# power_unit.net
KiCad netlist of a schematic drawn in Altium Designer
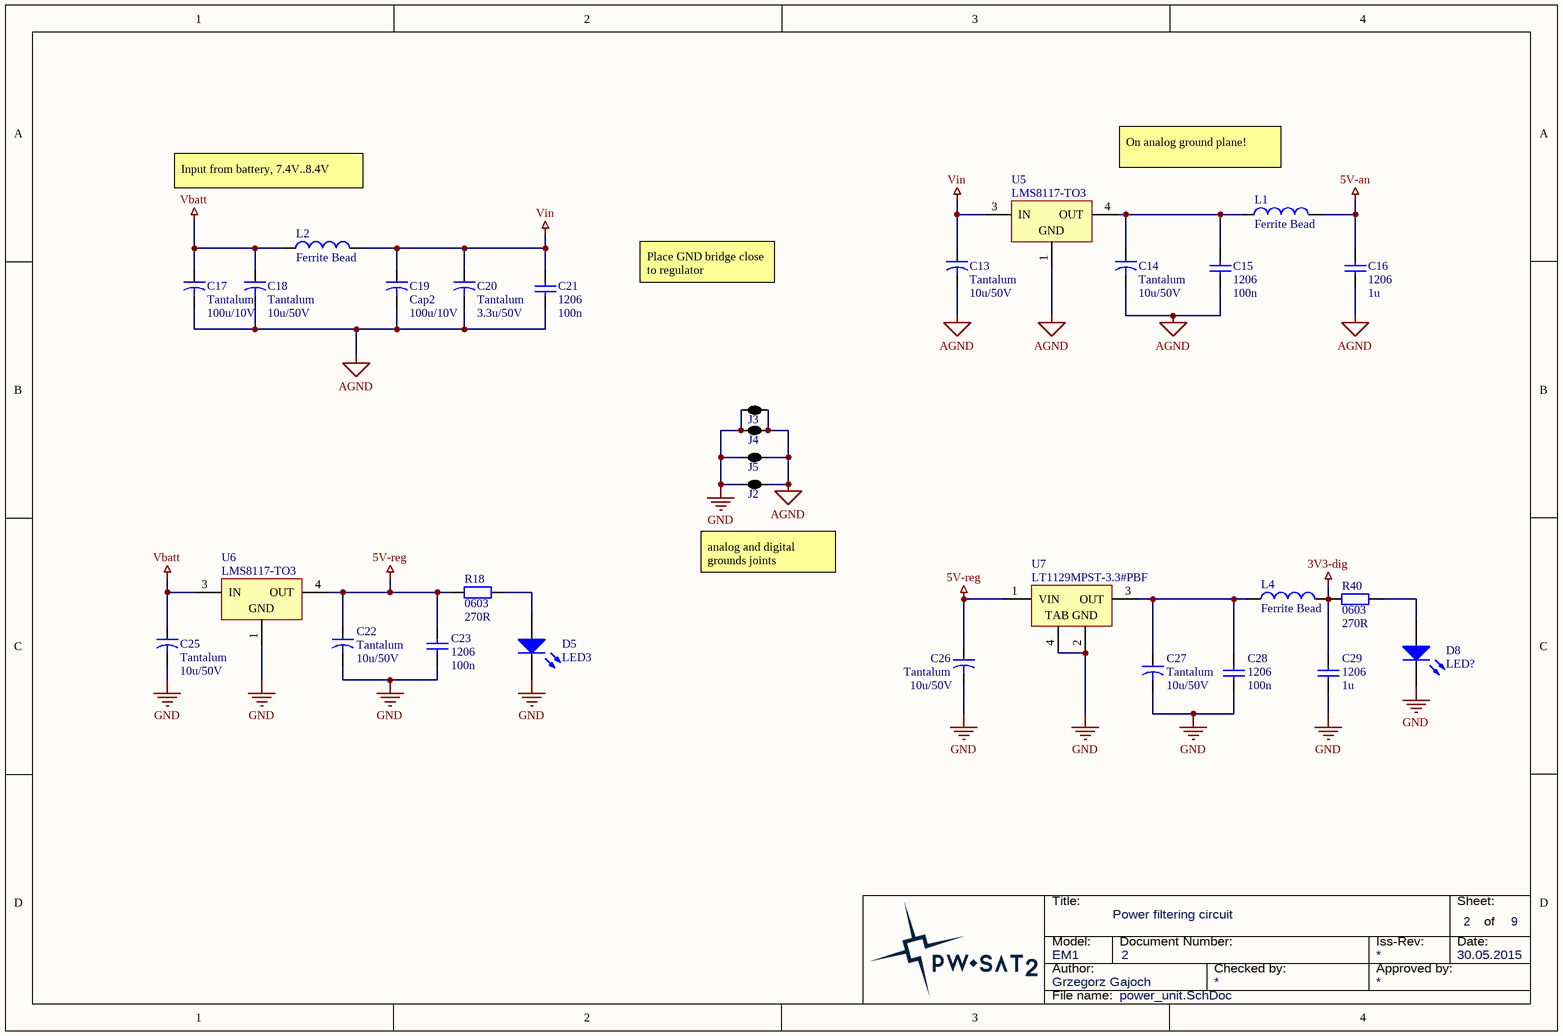
[diagram p0: power_unit.SchDoc]

(export (version "E")
  (design (tool "Eeschema 10.0.6"))
  (components
    (comp (ref "C13")
      (value "Tantalum")
      (footprint "Tantalum_cap_D")
      (description "Capacitor")
      (fields (field (name "ALTIUM_VALUE") "10u/50V") (field (name "PUBLISHER") "Altium Limited"))
      (libsource (lib "Miscellaneous Devices") (part "Cap2"))
    )
    (comp (ref "C14")
      (value "Tantalum")
      (footprint "Tantalum_cap_D")
      (description "Capacitor")
      (fields (field (name "ALTIUM_VALUE") "10u/50V") (field (name "PUBLISHER") "Altium Limited"))
      (libsource (lib "Miscellaneous Devices") (part "Cap2"))
    )
    (comp (ref "C15")
      (value "1206")
      (footprint "SMD_Capacitor_1206")
      (description "Capacitor")
      (fields (field (name "ALTIUM_VALUE") "100n") (field (name "PUBLISHER") "Altium Limited"))
      (libsource (lib "Miscellaneous Devices") (part "Cap"))
    )
    (comp (ref "C16")
      (value "1206")
      (footprint "SMD_Capacitor_1206")
      (description "Capacitor")
      (fields (field (name "ALTIUM_VALUE") "1u") (field (name "PUBLISHER") "Altium Limited"))
      (libsource (lib "Miscellaneous Devices") (part "Cap"))
    )
    (comp (ref "C17")
      (value "Tantalum")
      (footprint "Tantalum_cap_D")
      (description "Capacitor")
      (fields (field (name "ALTIUM_VALUE") "100u/10V") (field (name "PUBLISHER") "Altium Limited"))
      (libsource (lib "Miscellaneous Devices") (part "Cap2"))
    )
    (comp (ref "C18")
      (value "Tantalum")
      (footprint "Tantalum_cap_D")
      (description "Capacitor")
      (fields (field (name "ALTIUM_VALUE") "10u/50V") (field (name "PUBLISHER") "Altium Limited"))
      (libsource (lib "Miscellaneous Devices") (part "Cap2"))
    )
    (comp (ref "C19")
      (value "Cap2")
      (footprint "Tantalum_cap_D")
      (description "Capacitor")
      (fields (field (name "ALTIUM_VALUE") "100u/10V") (field (name "PUBLISHER") "Altium Limited"))
      (libsource (lib "Miscellaneous Devices") (part "Cap2"))
    )
    (comp (ref "C20")
      (value "Tantalum")
      (footprint "Tantalum_cap_D")
      (description "Capacitor")
      (fields (field (name "ALTIUM_VALUE") "3.3u/50V") (field (name "PUBLISHER") "Altium Limited"))
      (libsource (lib "Miscellaneous Devices") (part "Cap2"))
    )
    (comp (ref "C21")
      (value "1206")
      (footprint "SMD_Capacitor_1206")
      (description "Capacitor")
      (fields (field (name "ALTIUM_VALUE") "100n") (field (name "PUBLISHER") "Altium Limited"))
      (libsource (lib "Miscellaneous Devices") (part "Cap"))
    )
    (comp (ref "C22")
      (value "Tantalum")
      (footprint "Tantalum_cap_D")
      (description "Capacitor")
      (fields (field (name "ALTIUM_VALUE") "10u/50V") (field (name "PUBLISHER") "Altium Limited"))
      (libsource (lib "Miscellaneous Devices") (part "Cap2"))
    )
    (comp (ref "C23")
      (value "1206")
      (footprint "SMD_Capacitor_1206")
      (description "Capacitor")
      (fields (field (name "ALTIUM_VALUE") "100n") (field (name "PUBLISHER") "Altium Limited"))
      (libsource (lib "Miscellaneous Devices") (part "Cap"))
    )
    (comp (ref "C25")
      (value "Tantalum")
      (footprint "Tantalum_cap_D")
      (description "Capacitor")
      (fields (field (name "ALTIUM_VALUE") "10u/50V") (field (name "PUBLISHER") "Altium Limited"))
      (libsource (lib "Miscellaneous Devices") (part "Cap2"))
    )
    (comp (ref "C26")
      (value "Tantalum")
      (footprint "Tantalum_cap_D")
      (description "Capacitor")
      (fields (field (name "ALTIUM_VALUE") "10u/50V") (field (name "PUBLISHER") "Altium Limited"))
      (libsource (lib "Miscellaneous Devices") (part "Cap2"))
    )
    (comp (ref "C27")
      (value "Tantalum")
      (footprint "Tantalum_cap_D")
      (description "Capacitor")
      (fields (field (name "ALTIUM_VALUE") "10u/50V") (field (name "PUBLISHER") "Altium Limited"))
      (libsource (lib "Miscellaneous Devices") (part "Cap2"))
    )
    (comp (ref "C28")
      (value "1206")
      (footprint "SMD_Capacitor_1206")
      (description "Capacitor")
      (fields (field (name "ALTIUM_VALUE") "100n") (field (name "PUBLISHER") "Altium Limited"))
      (libsource (lib "Miscellaneous Devices") (part "Cap"))
    )
    (comp (ref "C29")
      (value "1206")
      (footprint "SMD_Capacitor_1206")
      (description "Capacitor")
      (fields (field (name "ALTIUM_VALUE") "1u") (field (name "PUBLISHER") "Altium Limited"))
      (libsource (lib "Miscellaneous Devices") (part "Cap"))
    )
    (comp (ref "D5")
      (value "LED3")
      (footprint "LED 0805 RED")
      (description "Typical BLUE SiC LED")
      (fields (field (name "PUBLISHER") "Altium Limited"))
      (libsource (lib "Miscellaneous Devices") (part "LED3"))
    )
    (comp (ref "D8")
      (value "LED?")
      (footprint "LED 0805 RED")
      (description "Typical BLUE SiC LED")
      (fields (field (name "PUBLISHER") "Altium Limited"))
      (libsource (lib "Miscellaneous Devices") (part "LED3"))
    )
    (comp (ref "J2")
      (value "2 way net tie junction")
      (footprint "2way_MP")
      (libsource (lib "NetTieLib") (part "2way"))
    )
    (comp (ref "J3")
      (value "2 way net tie junction")
      (footprint "2way_MP")
      (libsource (lib "NetTieLib") (part "2way"))
    )
    (comp (ref "J4")
      (value "2 way net tie junction")
      (footprint "2way_MP")
      (libsource (lib "NetTieLib") (part "2way"))
    )
    (comp (ref "J5")
      (value "2 way net tie junction")
      (footprint "2way_MP")
      (libsource (lib "NetTieLib") (part "2way"))
    )
    (comp (ref "L1")
      (value "Ferrite Bead")
      (footprint "Ferrite 1206")
      (description "Inductor")
      (fields (field (name "PUBLISHER") "Altium Limited"))
      (libsource (lib "Miscellaneous Devices") (part "Inductor"))
    )
    (comp (ref "L2")
      (value "Ferrite Bead")
      (footprint "Ferrite 1206")
      (description "Inductor")
      (fields (field (name "PUBLISHER") "Altium Limited"))
      (libsource (lib "Miscellaneous Devices") (part "Inductor"))
    )
    (comp (ref "L4")
      (value "Ferrite Bead")
      (footprint "Ferrite 1206")
      (description "Inductor")
      (fields (field (name "PUBLISHER") "Altium Limited"))
      (libsource (lib "Miscellaneous Devices") (part "Inductor"))
    )
    (comp (ref "R18")
      (value "0603")
      (footprint "SMD_Resistor_0603")
      (description "Resistor")
      (fields (field (name "ALTIUM_VALUE") "270R") (field (name "PUBLISHER") "Altium Limited"))
      (libsource (lib "Miscellaneous Devices") (part "Res2"))
    )
    (comp (ref "R40")
      (value "0603")
      (footprint "SMD_Resistor_0603")
      (description "Resistor")
      (fields (field (name "ALTIUM_VALUE") "270R") (field (name "PUBLISHER") "Altium Limited"))
      (libsource (lib "Miscellaneous Devices") (part "Res2"))
    )
    (comp (ref "U5")
      (value "LMS8117-TO3")
      (footprint "TD03B_M")
      (libsource (lib "microcircuits_linear-voltage-regulator") (part "LMS8117-TO3"))
    )
    (comp (ref "U6")
      (value "LMS8117-TO3")
      (footprint "TD03B_M")
      (libsource (lib "microcircuits_linear-voltage-regulator") (part "LMS8117-TO3"))
    )
    (comp (ref "U7")
      (value "LT1129MPST-3.3#PBF")
      (footprint "LT-ST-3-SOT-223_N")
      (fields (field (name "MANUFACTURER") "Linear Technology"))
      (libsource (lib "microcircuits_linear-voltage-regulator") (part "LT1129MPST-3.3#PBF"))
    )
  )
  (nets
    (net (code "1") (name "3V3-dig") (class "Default")
      (node (ref "C29") (pin "2") (pinfunction "2_2") (pintype "passive"))
      (node (ref "L4") (pin "2") (pinfunction "2_2") (pintype "passive"))
      (node (ref "R40") (pin "2") (pinfunction "2_2") (pintype "passive"))
    )
    (net (code "2") (name "5V-an") (class "Default")
      (node (ref "C16") (pin "2") (pinfunction "2_2") (pintype "passive"))
      (node (ref "L1") (pin "2") (pinfunction "2_2") (pintype "passive"))
    )
    (net (code "3") (name "5V-reg") (class "Default")
      (node (ref "C22") (pin "1") (pinfunction "1_1") (pintype "passive"))
      (node (ref "C23") (pin "2") (pinfunction "2_2") (pintype "passive"))
      (node (ref "C26") (pin "1") (pinfunction "1_1") (pintype "passive"))
      (node (ref "R18") (pin "2") (pinfunction "2_2") (pintype "passive"))
      (node (ref "U6") (pin "4") (pinfunction "OUT_4") (pintype "power_in"))
      (node (ref "U7") (pin "1") (pinfunction "VIN_1") (pintype "power_in"))
    )
    (net (code "4") (name "AGND") (class "Default")
      (node (ref "C13") (pin "2") (pinfunction "2_2") (pintype "passive"))
      (node (ref "C14") (pin "2") (pinfunction "2_2") (pintype "passive"))
      (node (ref "C15") (pin "1") (pinfunction "1_1") (pintype "passive"))
      (node (ref "C16") (pin "1") (pinfunction "1_1") (pintype "passive"))
      (node (ref "C17") (pin "2") (pinfunction "2_2") (pintype "passive"))
      (node (ref "C18") (pin "2") (pinfunction "2_2") (pintype "passive"))
      (node (ref "C19") (pin "2") (pinfunction "2_2") (pintype "passive"))
      (node (ref "C20") (pin "2") (pinfunction "2_2") (pintype "passive"))
      (node (ref "C21") (pin "1") (pinfunction "1_1") (pintype "passive"))
      (node (ref "J2") (pin "2") (pinfunction "2_2") (pintype "passive"))
      (node (ref "J3") (pin "2") (pinfunction "2_2") (pintype "passive"))
      (node (ref "J4") (pin "2") (pinfunction "2_2") (pintype "passive"))
      (node (ref "J5") (pin "2") (pinfunction "2_2") (pintype "passive"))
      (node (ref "U5") (pin "1") (pinfunction "GND_1") (pintype "power_in"))
    )
    (net (code "5") (name "GND") (class "Default")
      (node (ref "C22") (pin "2") (pinfunction "2_2") (pintype "passive"))
      (node (ref "C23") (pin "1") (pinfunction "1_1") (pintype "passive"))
      (node (ref "C25") (pin "2") (pinfunction "2_2") (pintype "passive"))
      (node (ref "C26") (pin "2") (pinfunction "2_2") (pintype "passive"))
      (node (ref "C27") (pin "2") (pinfunction "2_2") (pintype "passive"))
      (node (ref "C28") (pin "1") (pinfunction "1_1") (pintype "passive"))
      (node (ref "C29") (pin "1") (pinfunction "1_1") (pintype "passive"))
      (node (ref "D5") (pin "2") (pinfunction "K_2") (pintype "passive"))
      (node (ref "D8") (pin "2") (pinfunction "K_2") (pintype "passive"))
      (node (ref "J2") (pin "1") (pinfunction "1_1") (pintype "passive"))
      (node (ref "J3") (pin "1") (pinfunction "1_1") (pintype "passive"))
      (node (ref "J4") (pin "1") (pinfunction "1_1") (pintype "passive"))
      (node (ref "J5") (pin "1") (pinfunction "1_1") (pintype "passive"))
      (node (ref "U6") (pin "1") (pinfunction "GND_1") (pintype "power_in"))
      (node (ref "U7") (pin "2") (pinfunction "GND_2") (pintype "power_in"))
      (node (ref "U7") (pin "4") (pinfunction "TAB_4") (pintype "power_in"))
    )
    (net (code "6") (name "Net-(D5-A)") (class "Default")
      (node (ref "D5") (pin "1") (pinfunction "A_1") (pintype "passive"))
      (node (ref "R18") (pin "1") (pinfunction "1_1") (pintype "passive"))
    )
    (net (code "7") (name "Net-(D8-A)") (class "Default")
      (node (ref "D8") (pin "1") (pinfunction "A_1") (pintype "passive"))
      (node (ref "R40") (pin "1") (pinfunction "1_1") (pintype "passive"))
    )
    (net (code "8") (name "Net-(U5-OUT)") (class "Default")
      (node (ref "C14") (pin "1") (pinfunction "1_1") (pintype "passive"))
      (node (ref "C15") (pin "2") (pinfunction "2_2") (pintype "passive"))
      (node (ref "L1") (pin "1") (pinfunction "1_1") (pintype "passive"))
      (node (ref "U5") (pin "4") (pinfunction "OUT_4") (pintype "power_in"))
    )
    (net (code "9") (name "Net-(U7-OUT)") (class "Default")
      (node (ref "C27") (pin "1") (pinfunction "1_1") (pintype "passive"))
      (node (ref "C28") (pin "2") (pinfunction "2_2") (pintype "passive"))
      (node (ref "L4") (pin "1") (pinfunction "1_1") (pintype "passive"))
      (node (ref "U7") (pin "3") (pinfunction "OUT_3") (pintype "power_in"))
    )
    (net (code "10") (name "Vbatt") (class "Default")
      (node (ref "C17") (pin "1") (pinfunction "1_1") (pintype "passive"))
      (node (ref "C18") (pin "1") (pinfunction "1_1") (pintype "passive"))
      (node (ref "C25") (pin "1") (pinfunction "1_1") (pintype "passive"))
      (node (ref "L2") (pin "1") (pinfunction "1_1") (pintype "passive"))
      (node (ref "U6") (pin "3") (pinfunction "IN_3") (pintype "power_in"))
    )
    (net (code "11") (name "Vin") (class "Default")
      (node (ref "C13") (pin "1") (pinfunction "1_1") (pintype "passive"))
      (node (ref "C19") (pin "1") (pinfunction "1_1") (pintype "passive"))
      (node (ref "C20") (pin "1") (pinfunction "1_1") (pintype "passive"))
      (node (ref "C21") (pin "2") (pinfunction "2_2") (pintype "passive"))
      (node (ref "L2") (pin "2") (pinfunction "2_2") (pintype "passive"))
      (node (ref "U5") (pin "3") (pinfunction "IN_3") (pintype "power_in"))
    )
  )
)
